# smartmeterif_2.net
KiCad netlist of a schematic drawn in EAGLE
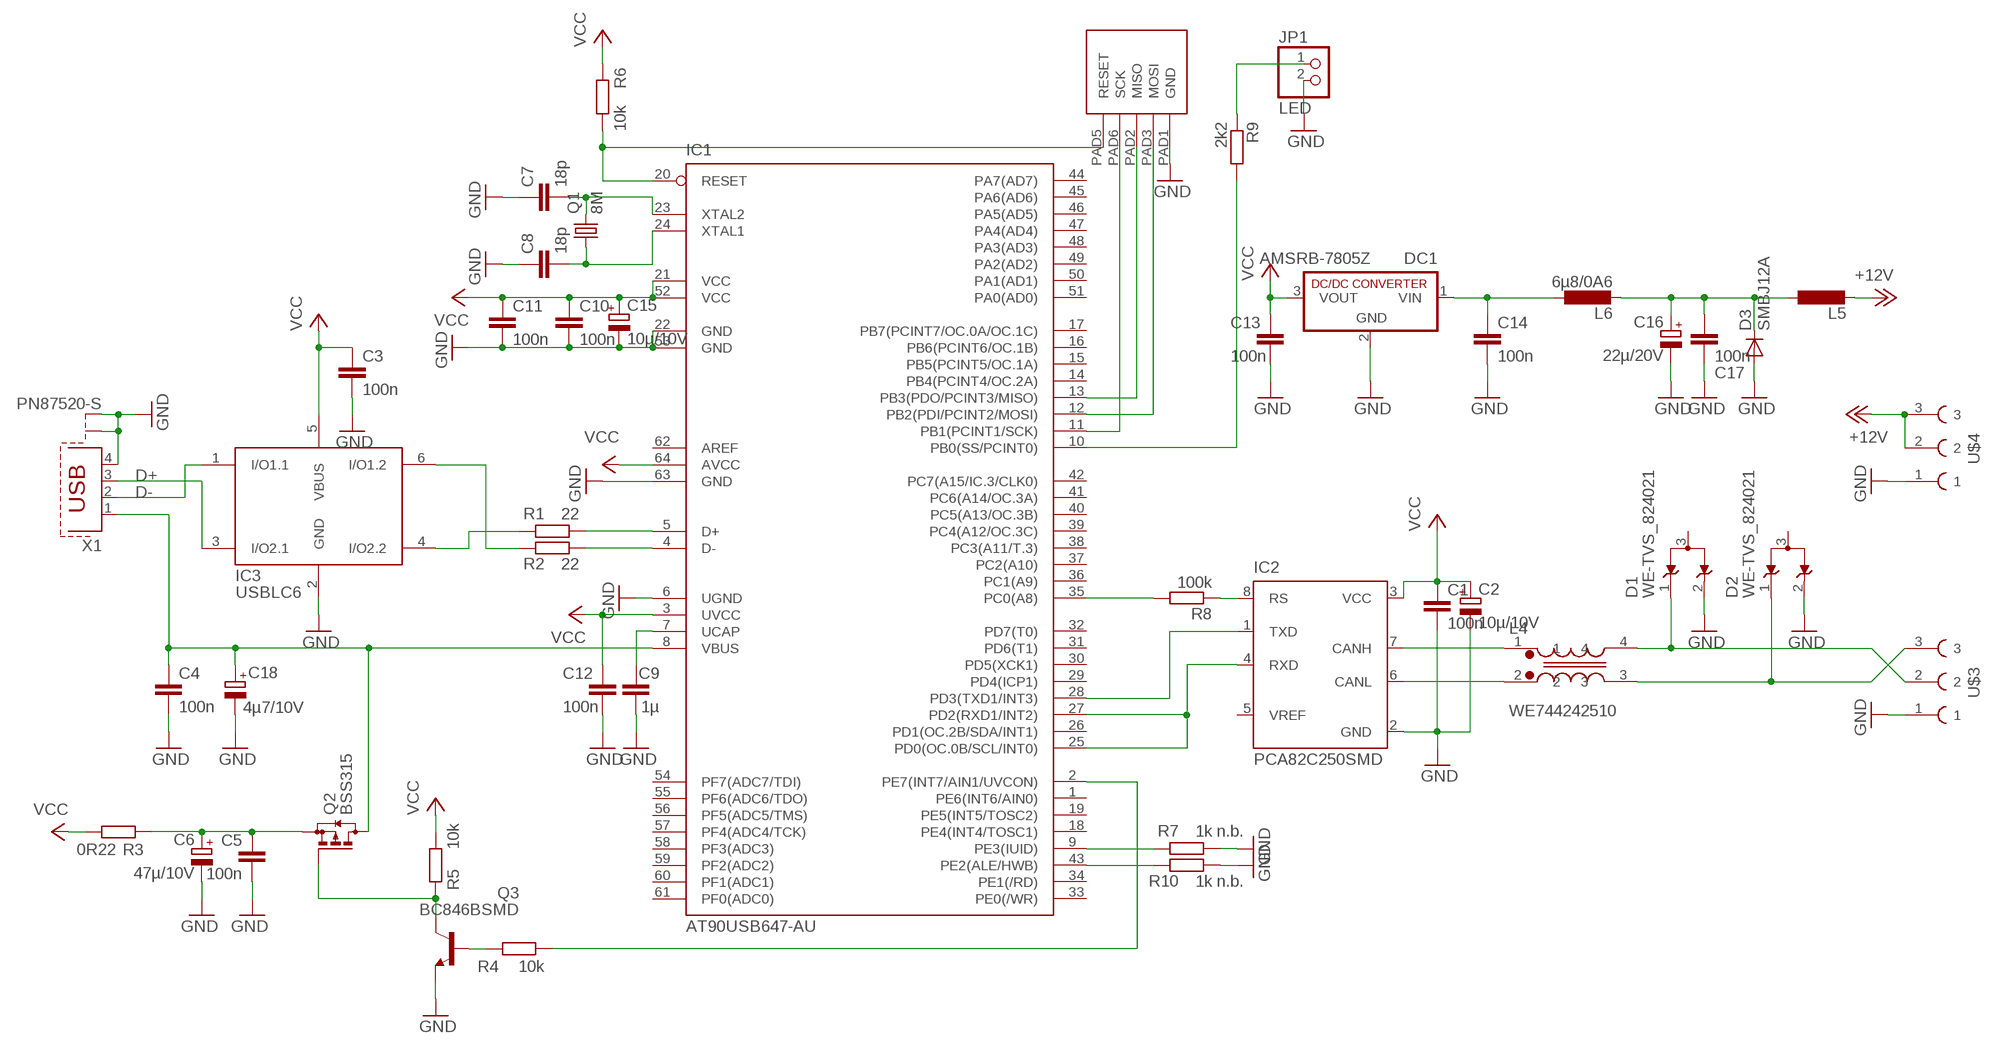
[diagram p0: schematic, sheet 1]

(export (version "E")
  (design (tool "Eeschema 10.0.6"))
  (components
    (comp (ref "C1")
      (value "100n")
      (footprint "eagle-import:C0603")
      (libsource (lib "eagle-import") (part "resistor_C-EUC0603"))
    )
    (comp (ref "C2")
      (value "10µ/10V")
      (footprint "eagle-import:A_3216-18W")
      (libsource (lib "eagle-import") (part "CPOL-EUA/3216-18W"))
    )
    (comp (ref "C3")
      (value "100n")
      (footprint "eagle-import:C0603")
      (libsource (lib "eagle-import") (part "resistor_C-EUC0603"))
    )
    (comp (ref "C4")
      (value "100n")
      (footprint "eagle-import:C0603")
      (libsource (lib "eagle-import") (part "resistor_C-EUC0603"))
    )
    (comp (ref "C5")
      (value "100n")
      (footprint "eagle-import:C0603")
      (libsource (lib "eagle-import") (part "resistor_C-EUC0603"))
    )
    (comp (ref "C6")
      (value "47µ/10V")
      (footprint "eagle-import:SMC_C")
      (libsource (lib "eagle-import") (part "CPOL-EUSMCC"))
    )
    (comp (ref "C7")
      (value "18p")
      (footprint "eagle-import:C0603")
      (libsource (lib "eagle-import") (part "C-EUC0603"))
    )
    (comp (ref "C8")
      (value "18p")
      (footprint "eagle-import:C0603")
      (libsource (lib "eagle-import") (part "C-EUC0603"))
    )
    (comp (ref "C9")
      (value "1µ")
      (footprint "eagle-import:C1210K")
      (libsource (lib "eagle-import") (part "C-EUC1210K"))
    )
    (comp (ref "C10")
      (value "100n")
      (footprint "eagle-import:C0603")
      (libsource (lib "eagle-import") (part "resistor_C-EUC0603"))
    )
    (comp (ref "C11")
      (value "100n")
      (footprint "eagle-import:C0603")
      (libsource (lib "eagle-import") (part "resistor_C-EUC0603"))
    )
    (comp (ref "C12")
      (value "100n")
      (footprint "eagle-import:C0603")
      (libsource (lib "eagle-import") (part "resistor_C-EUC0603"))
    )
    (comp (ref "C13")
      (value "100n")
      (footprint "eagle-import:C0603")
      (libsource (lib "eagle-import") (part "resistor_C-EUC0603"))
    )
    (comp (ref "C14")
      (value "100n")
      (footprint "eagle-import:C0603")
      (libsource (lib "eagle-import") (part "resistor_C-EUC0603"))
    )
    (comp (ref "C15")
      (value "10µ/10V")
      (footprint "eagle-import:A_3216-18W")
      (libsource (lib "eagle-import") (part "CPOL-EUA/3216-18W"))
    )
    (comp (ref "C16")
      (value "22µ/20V")
      (footprint "eagle-import:SMC_C")
      (libsource (lib "eagle-import") (part "CPOL-EUSMCC"))
    )
    (comp (ref "C17")
      (value "100n")
      (footprint "eagle-import:C0603")
      (libsource (lib "eagle-import") (part "resistor_C-EUC0603"))
    )
    (comp (ref "C18")
      (value "4µ7/10V")
      (footprint "eagle-import:SMC_A")
      (libsource (lib "eagle-import") (part "CPOL-EUSMCA"))
    )
    (comp (ref "D1")
      (value "WE-TVS_824021")
      (footprint "eagle-import:WE-TVS_SOT23-3L")
      (libsource (lib "eagle-import") (part "WE-TVS_824021"))
    )
    (comp (ref "D2")
      (value "WE-TVS_824021")
      (footprint "eagle-import:WE-TVS_SOT23-3L")
      (libsource (lib "eagle-import") (part "WE-TVS_824021"))
    )
    (comp (ref "D3")
      (value "SMBJ12A")
      (footprint "eagle-import:SMB")
      (libsource (lib "eagle-import") (part "DIODE-SMB"))
    )
    (comp (ref "DC1")
      (value "AMSRB-7805Z")
      (footprint "eagle-import:SIP3")
      (libsource (lib "eagle-import") (part "R-78C-1.05.0"))
    )
    (comp (ref "IC1")
      (value "AT90USB647-AU")
      (footprint "eagle-import:TQFP64")
      (libsource (lib "eagle-import") (part "AT90USB647-AU"))
    )
    (comp (ref "IC2")
      (value "PCA82C250SMD")
      (footprint "eagle-import:SO8")
      (libsource (lib "eagle-import") (part "PCA82C250SMD"))
    )
    (comp (ref "IC3")
      (value "USBLC6")
      (footprint "eagle-import:SOT23-6L")
      (libsource (lib "eagle-import") (part "USBLC6"))
    )
    (comp (ref "JP1")
      (value "LED")
      (footprint "eagle-import:1X02")
      (libsource (lib "eagle-import") (part "PINHD-1X2"))
    )
    (comp (ref "L4")
      (value "WE744242510")
      (footprint "eagle-import:WE-SLM")
      (libsource (lib "eagle-import") (part "WE-SLM"))
    )
    (comp (ref "L5")
      (value "L-EUL1806")
      (footprint "eagle-import:L1806")
      (libsource (lib "eagle-import") (part "L-EUL1806"))
    )
    (comp (ref "L6")
      (value "6µ8/0A6")
      (footprint "eagle-import:L1812")
      (libsource (lib "eagle-import") (part "rcl_L-EUL1812"))
    )
    (comp (ref "Q1")
      (value "8M")
      (footprint "eagle-import:SM49")
      (libsource (lib "eagle-import") (part "CRYSTALSM49"))
    )
    (comp (ref "Q2")
      (value "BSS315")
      (footprint "eagle-import:SOT23")
      (libsource (lib "eagle-import") (part "BSS84"))
    )
    (comp (ref "Q3")
      (value "BC846BSMD")
      (footprint "eagle-import:SOT23")
      (libsource (lib "eagle-import") (part "BC846SMDB"))
    )
    (comp (ref "R1")
      (value "22")
      (footprint "eagle-import:R0603")
      (libsource (lib "eagle-import") (part "R-EU_R0603"))
    )
    (comp (ref "R2")
      (value "22")
      (footprint "eagle-import:R0603")
      (libsource (lib "eagle-import") (part "R-EU_R0603"))
    )
    (comp (ref "R3")
      (value "0R22")
      (footprint "eagle-import:R0603")
      (libsource (lib "eagle-import") (part "R-EU_R0603"))
    )
    (comp (ref "R4")
      (value "10k")
      (footprint "eagle-import:R0603")
      (libsource (lib "eagle-import") (part "R-EU_R0603"))
    )
    (comp (ref "R5")
      (value "10k")
      (footprint "eagle-import:R0603")
      (libsource (lib "eagle-import") (part "R-EU_R0603"))
    )
    (comp (ref "R6")
      (value "10k")
      (footprint "eagle-import:R0603")
      (libsource (lib "eagle-import") (part "R-EU_R0603"))
    )
    (comp (ref "R7")
      (value "1k n.b.")
      (footprint "eagle-import:R0603")
      (libsource (lib "eagle-import") (part "R-EU_R0603"))
    )
    (comp (ref "R8")
      (value "100k")
      (footprint "eagle-import:R0603")
      (libsource (lib "eagle-import") (part "resistor_R-EU_R0603"))
    )
    (comp (ref "R9")
      (value "2k2")
      (footprint "eagle-import:R0603")
      (libsource (lib "eagle-import") (part "resistor_R-EU_R0603"))
    )
    (comp (ref "R10")
      (value "1k n.b.")
      (footprint "eagle-import:R0603")
      (libsource (lib "eagle-import") (part "R-EU_R0603"))
    )
    (comp (ref "U$2")
      (value "ATMEL_ISP")
      (footprint "eagle-import:ATMEL_ISP")
      (libsource (lib "eagle-import") (part "ATMEL_ISP"))
    )
    (comp (ref "U$3")
      (value "MKDSO_2.5/3_L")
      (footprint "eagle-import:PHOENIX_MKDSO_2.5_3_L")
      (libsource (lib "eagle-import") (part "MKDSO_2.5/3_L"))
    )
    (comp (ref "U$4")
      (value "MKDSO_2.5/3_L")
      (footprint "eagle-import:PHOENIX_MKDSO_2.5_3_L")
      (libsource (lib "eagle-import") (part "MKDSO_2.5/3_L"))
    )
    (comp (ref "X1")
      (value "PN87520-S")
      (footprint "eagle-import:PN87520-S")
      (libsource (lib "eagle-import") (part "PN87520-S"))
    )
  )
  (nets
    (net (code "1") (name "+12V") (class "Default")
      (node (ref "L5") (pin "2") (pinfunction "2_2") (pintype "passive"))
      (node (ref "U$4") (pin "2") (pinfunction "2_2") (pintype "bidirectional"))
      (node (ref "U$4") (pin "3") (pinfunction "3_3") (pintype "bidirectional"))
    )
    (net (code "2") (name "/D+") (class "Default")
      (node (ref "IC3") (pin "3") (pinfunction "I/O2.1_3") (pintype "bidirectional"))
      (node (ref "X1") (pin "3") (pinfunction "3_3") (pintype "passive"))
    )
    (net (code "3") (name "/D-") (class "Default")
      (node (ref "IC3") (pin "1") (pinfunction "I/O1.1_1") (pintype "bidirectional"))
      (node (ref "X1") (pin "2") (pinfunction "2_2") (pintype "passive"))
    )
    (net (code "4") (name "GND") (class "Default")
      (node (ref "C1") (pin "2") (pinfunction "2_2") (pintype "passive"))
      (node (ref "C10") (pin "2") (pinfunction "2_2") (pintype "passive"))
      (node (ref "C11") (pin "2") (pinfunction "2_2") (pintype "passive"))
      (node (ref "C12") (pin "2") (pinfunction "2_2") (pintype "passive"))
      (node (ref "C13") (pin "2") (pinfunction "2_2") (pintype "passive"))
      (node (ref "C14") (pin "2") (pinfunction "2_2") (pintype "passive"))
      (node (ref "C15") (pin "-") (pinfunction "-_-") (pintype "passive"))
      (node (ref "C16") (pin "-") (pinfunction "-_-") (pintype "passive"))
      (node (ref "C17") (pin "2") (pinfunction "2_2") (pintype "passive"))
      (node (ref "C18") (pin "-") (pinfunction "-_-") (pintype "passive"))
      (node (ref "C2") (pin "-") (pinfunction "-_-") (pintype "passive"))
      (node (ref "C3") (pin "2") (pinfunction "2_2") (pintype "passive"))
      (node (ref "C4") (pin "2") (pinfunction "2_2") (pintype "passive"))
      (node (ref "C5") (pin "2") (pinfunction "2_2") (pintype "passive"))
      (node (ref "C6") (pin "-") (pinfunction "-_-") (pintype "passive"))
      (node (ref "C7") (pin "1") (pinfunction "1_1") (pintype "passive"))
      (node (ref "C8") (pin "1") (pinfunction "1_1") (pintype "passive"))
      (node (ref "C9") (pin "1") (pinfunction "1_1") (pintype "passive"))
      (node (ref "D1") (pin "2") (pinfunction "2_2") (pintype "passive"))
      (node (ref "D2") (pin "2") (pinfunction "2_2") (pintype "passive"))
      (node (ref "D3") (pin "A") (pinfunction "A_A") (pintype "passive"))
      (node (ref "DC1") (pin "2") (pinfunction "GND_2") (pintype "passive"))
      (node (ref "IC1") (pin "22") (pinfunction "GND_22") (pintype "power_in"))
      (node (ref "IC1") (pin "53") (pinfunction "GND_53") (pintype "power_in"))
      (node (ref "IC1") (pin "6") (pinfunction "UGND_6") (pintype "power_in"))
      (node (ref "IC1") (pin "63") (pinfunction "GND_63") (pintype "power_in"))
      (node (ref "IC2") (pin "2") (pinfunction "GND_2") (pintype "power_in"))
      (node (ref "IC3") (pin "2") (pinfunction "GND_2") (pintype "power_in"))
      (node (ref "JP1") (pin "2") (pinfunction "2_2") (pintype "passive"))
      (node (ref "Q3") (pin "2") (pinfunction "E_2") (pintype "passive"))
      (node (ref "R10") (pin "2") (pinfunction "2_2") (pintype "passive"))
      (node (ref "R7") (pin "2") (pinfunction "2_2") (pintype "passive"))
      (node (ref "U$2") (pin "PAD1") (pinfunction "GND_PAD1") (pintype "power_in"))
      (node (ref "U$3") (pin "1") (pinfunction "1_1") (pintype "bidirectional"))
      (node (ref "U$4") (pin "1") (pinfunction "1_1") (pintype "bidirectional"))
      (node (ref "X1") (pin "4") (pinfunction "4_4") (pintype "passive"))
      (node (ref "X1") (pin "S1") (pinfunction "S1_S1") (pintype "passive"))
      (node (ref "X1") (pin "S2") (pinfunction "S2_S2") (pintype "passive"))
    )
    (net (code "5") (name "Net-(C16-Pad+)") (class "Default")
      (node (ref "C16") (pin "+") (pinfunction "+_+") (pintype "passive"))
      (node (ref "C17") (pin "1") (pinfunction "1_1") (pintype "passive"))
      (node (ref "D3") (pin "C") (pinfunction "C_C") (pintype "passive"))
      (node (ref "L5") (pin "1") (pinfunction "1_1") (pintype "passive"))
      (node (ref "L6") (pin "2") (pinfunction "2_2") (pintype "passive"))
    )
    (net (code "6") (name "Net-(D1-Pad1)") (class "Default")
      (node (ref "D1") (pin "1") (pinfunction "1_1") (pintype "passive"))
      (node (ref "L4") (pin "4") (pinfunction "4_4") (pintype "bidirectional"))
      (node (ref "U$3") (pin "2") (pinfunction "2_2") (pintype "bidirectional"))
    )
    (net (code "7") (name "Net-(D2-Pad1)") (class "Default")
      (node (ref "D2") (pin "1") (pinfunction "1_1") (pintype "passive"))
      (node (ref "L4") (pin "3") (pinfunction "3_3") (pintype "bidirectional"))
      (node (ref "U$3") (pin "3") (pinfunction "3_3") (pintype "bidirectional"))
    )
    (net (code "8") (name "Net-(DC1-VIN)") (class "Default")
      (node (ref "C14") (pin "1") (pinfunction "1_1") (pintype "passive"))
      (node (ref "DC1") (pin "1") (pinfunction "VIN_1") (pintype "passive"))
      (node (ref "L6") (pin "1") (pinfunction "1_1") (pintype "passive"))
    )
    (net (code "9") (name "Net-(IC1-D+)") (class "Default")
      (node (ref "IC1") (pin "5") (pinfunction "D+_5") (pintype "bidirectional"))
      (node (ref "R1") (pin "2") (pinfunction "2_2") (pintype "passive"))
    )
    (net (code "10") (name "Net-(IC1-D-)") (class "Default")
      (node (ref "IC1") (pin "4") (pinfunction "D-_4") (pintype "bidirectional"))
      (node (ref "R2") (pin "2") (pinfunction "2_2") (pintype "passive"))
    )
    (net (code "11") (name "Net-(IC1-PB0(SS{slash}PCINT0))") (class "Default")
      (node (ref "IC1") (pin "10") (pinfunction "PB0(SS/PCINT0)_10") (pintype "bidirectional"))
      (node (ref "R9") (pin "2") (pinfunction "2_2") (pintype "passive"))
    )
    (net (code "12") (name "Net-(IC1-PB1(PCINT1{slash}SCK))") (class "Default")
      (node (ref "IC1") (pin "11") (pinfunction "PB1(PCINT1/SCK)_11") (pintype "bidirectional"))
      (node (ref "U$2") (pin "PAD6") (pinfunction "SCK_PAD6") (pintype "bidirectional"))
    )
    (net (code "13") (name "Net-(IC1-PB2(PDI{slash}PCINT2{slash}MOSI))") (class "Default")
      (node (ref "IC1") (pin "12") (pinfunction "PB2(PDI/PCINT2/MOSI)_12") (pintype "bidirectional"))
      (node (ref "U$2") (pin "PAD3") (pinfunction "MOSI_PAD3") (pintype "bidirectional"))
    )
    (net (code "14") (name "Net-(IC1-PB3(PDO{slash}PCINT3{slash}MISO))") (class "Default")
      (node (ref "IC1") (pin "13") (pinfunction "PB3(PDO/PCINT3/MISO)_13") (pintype "bidirectional"))
      (node (ref "U$2") (pin "PAD2") (pinfunction "MISO_PAD2") (pintype "bidirectional"))
    )
    (net (code "15") (name "Net-(IC1-PC0(A8))") (class "Default")
      (node (ref "IC1") (pin "35") (pinfunction "PC0(A8)_35") (pintype "bidirectional"))
      (node (ref "R8") (pin "2") (pinfunction "2_2") (pintype "passive"))
    )
    (net (code "16") (name "Net-(IC1-PD0(OC.0B{slash}SCL{slash}INT0))") (class "Default")
      (node (ref "IC1") (pin "25") (pinfunction "PD0(OC.0B/SCL/INT0)_25") (pintype "bidirectional"))
      (node (ref "IC1") (pin "27") (pinfunction "PD2(RXD1/INT2)_27") (pintype "bidirectional"))
      (node (ref "IC2") (pin "4") (pinfunction "RXD_4") (pintype "output"))
    )
    (net (code "17") (name "Net-(IC1-PD3(TXD1{slash}INT3))") (class "Default")
      (node (ref "IC1") (pin "28") (pinfunction "PD3(TXD1/INT3)_28") (pintype "bidirectional"))
      (node (ref "IC2") (pin "1") (pinfunction "TXD_1") (pintype "input"))
    )
    (net (code "18") (name "Net-(IC1-PE2(ALE{slash}HWB))") (class "Default")
      (node (ref "IC1") (pin "43") (pinfunction "PE2(ALE/HWB)_43") (pintype "bidirectional"))
      (node (ref "R10") (pin "1") (pinfunction "1_1") (pintype "passive"))
    )
    (net (code "19") (name "Net-(IC1-PE3(IUID))") (class "Default")
      (node (ref "IC1") (pin "9") (pinfunction "PE3(IUID)_9") (pintype "bidirectional"))
      (node (ref "R7") (pin "1") (pinfunction "1_1") (pintype "passive"))
    )
    (net (code "20") (name "Net-(IC1-PE7(INT7{slash}AIN1{slash}UVCON))") (class "Default")
      (node (ref "IC1") (pin "2") (pinfunction "PE7(INT7/AIN1/UVCON)_2") (pintype "bidirectional"))
      (node (ref "R4") (pin "2") (pinfunction "2_2") (pintype "passive"))
    )
    (net (code "21") (name "Net-(IC1-RESET)") (class "Default")
      (node (ref "IC1") (pin "20") (pinfunction "RESET_20") (pintype "input"))
      (node (ref "R6") (pin "2") (pinfunction "2_2") (pintype "passive"))
      (node (ref "U$2") (pin "PAD5") (pinfunction "RESET_PAD5") (pintype "bidirectional"))
    )
    (net (code "22") (name "Net-(IC1-UCAP)") (class "Default")
      (node (ref "C9") (pin "2") (pinfunction "2_2") (pintype "passive"))
      (node (ref "IC1") (pin "7") (pinfunction "UCAP_7") (pintype "power_in"))
    )
    (net (code "23") (name "Net-(IC1-VBUS)") (class "Default")
      (node (ref "C18") (pin "+") (pinfunction "+_+") (pintype "passive"))
      (node (ref "C4") (pin "1") (pinfunction "1_1") (pintype "passive"))
      (node (ref "IC1") (pin "8") (pinfunction "VBUS_8") (pintype "power_in"))
      (node (ref "Q2") (pin "3") (pinfunction "D_3") (pintype "passive"))
      (node (ref "X1") (pin "1") (pinfunction "1_1") (pintype "passive"))
    )
    (net (code "24") (name "Net-(IC1-XTAL1)") (class "Default")
      (node (ref "C8") (pin "2") (pinfunction "2_2") (pintype "passive"))
      (node (ref "IC1") (pin "24") (pinfunction "XTAL1_24") (pintype "bidirectional"))
      (node (ref "Q1") (pin "1") (pinfunction "1_1") (pintype "passive"))
    )
    (net (code "25") (name "Net-(IC1-XTAL2)") (class "Default")
      (node (ref "C7") (pin "2") (pinfunction "2_2") (pintype "passive"))
      (node (ref "IC1") (pin "23") (pinfunction "XTAL2_23") (pintype "bidirectional"))
      (node (ref "Q1") (pin "2") (pinfunction "2_2") (pintype "passive"))
    )
    (net (code "26") (name "Net-(IC2-CANH)") (class "Default")
      (node (ref "IC2") (pin "7") (pinfunction "CANH_7") (pintype "bidirectional"))
      (node (ref "L4") (pin "1") (pinfunction "1_1") (pintype "bidirectional"))
    )
    (net (code "27") (name "Net-(IC2-CANL)") (class "Default")
      (node (ref "IC2") (pin "6") (pinfunction "CANL_6") (pintype "bidirectional"))
      (node (ref "L4") (pin "2") (pinfunction "2_2") (pintype "bidirectional"))
    )
    (net (code "28") (name "Net-(IC2-RS)") (class "Default")
      (node (ref "IC2") (pin "8") (pinfunction "RS_8") (pintype "input"))
      (node (ref "R8") (pin "1") (pinfunction "1_1") (pintype "passive"))
    )
    (net (code "29") (name "Net-(IC3-I{slash}O1.2)") (class "Default")
      (node (ref "IC3") (pin "6") (pinfunction "I/O1.2_6") (pintype "bidirectional"))
      (node (ref "R2") (pin "1") (pinfunction "1_1") (pintype "passive"))
    )
    (net (code "30") (name "Net-(IC3-I{slash}O2.2)") (class "Default")
      (node (ref "IC3") (pin "4") (pinfunction "I/O2.2_4") (pintype "bidirectional"))
      (node (ref "R1") (pin "1") (pinfunction "1_1") (pintype "passive"))
    )
    (net (code "31") (name "Net-(JP1-Pad1)") (class "Default")
      (node (ref "JP1") (pin "1") (pinfunction "1_1") (pintype "passive"))
      (node (ref "R9") (pin "1") (pinfunction "1_1") (pintype "passive"))
    )
    (net (code "32") (name "Net-(Q2-G)") (class "Default")
      (node (ref "Q2") (pin "1") (pinfunction "G_1") (pintype "passive"))
      (node (ref "Q3") (pin "3") (pinfunction "C_3") (pintype "passive"))
      (node (ref "R5") (pin "1") (pinfunction "1_1") (pintype "passive"))
    )
    (net (code "33") (name "Net-(Q2-S)") (class "Default")
      (node (ref "C5") (pin "1") (pinfunction "1_1") (pintype "passive"))
      (node (ref "C6") (pin "+") (pinfunction "+_+") (pintype "passive"))
      (node (ref "Q2") (pin "2") (pinfunction "S_2") (pintype "passive"))
      (node (ref "R3") (pin "1") (pinfunction "1_1") (pintype "passive"))
    )
    (net (code "34") (name "Net-(Q3-B)") (class "Default")
      (node (ref "Q3") (pin "1") (pinfunction "B_1") (pintype "passive"))
      (node (ref "R4") (pin "1") (pinfunction "1_1") (pintype "passive"))
    )
    (net (code "35") (name "VCC") (class "Default")
      (node (ref "C1") (pin "1") (pinfunction "1_1") (pintype "passive"))
      (node (ref "C10") (pin "1") (pinfunction "1_1") (pintype "passive"))
      (node (ref "C11") (pin "1") (pinfunction "1_1") (pintype "passive"))
      (node (ref "C12") (pin "1") (pinfunction "1_1") (pintype "passive"))
      (node (ref "C13") (pin "1") (pinfunction "1_1") (pintype "passive"))
      (node (ref "C15") (pin "+") (pinfunction "+_+") (pintype "passive"))
      (node (ref "C2") (pin "+") (pinfunction "+_+") (pintype "passive"))
      (node (ref "C3") (pin "1") (pinfunction "1_1") (pintype "passive"))
      (node (ref "DC1") (pin "3") (pinfunction "VOUT_3") (pintype "passive"))
      (node (ref "IC1") (pin "21") (pinfunction "VCC_21") (pintype "power_in"))
      (node (ref "IC1") (pin "3") (pinfunction "UVCC_3") (pintype "power_in"))
      (node (ref "IC1") (pin "52") (pinfunction "VCC_52") (pintype "power_in"))
      (node (ref "IC1") (pin "64") (pinfunction "AVCC_64") (pintype "bidirectional"))
      (node (ref "IC2") (pin "3") (pinfunction "VCC_3") (pintype "power_in"))
      (node (ref "IC3") (pin "5") (pinfunction "VBUS_5") (pintype "power_in"))
      (node (ref "R3") (pin "2") (pinfunction "2_2") (pintype "passive"))
      (node (ref "R5") (pin "2") (pinfunction "2_2") (pintype "passive"))
      (node (ref "R6") (pin "1") (pinfunction "1_1") (pintype "passive"))
    )
    (net (code "36") (name "unconnected-(D1-GND-Pad3)") (class "Default")
      (node (ref "D1") (pin "3") (pinfunction "GND_3") (pintype "passive"))
    )
    (net (code "37") (name "unconnected-(D2-GND-Pad3)") (class "Default")
      (node (ref "D2") (pin "3") (pinfunction "GND_3") (pintype "passive"))
    )
    (net (code "38") (name "unconnected-(IC1-AREF-Pad62)") (class "Default")
      (node (ref "IC1") (pin "62") (pinfunction "AREF_62") (pintype "bidirectional"))
    )
    (net (code "39") (name "unconnected-(IC1-PA0(AD0)-Pad51)") (class "Default")
      (node (ref "IC1") (pin "51") (pinfunction "PA0(AD0)_51") (pintype "bidirectional"))
    )
    (net (code "40") (name "unconnected-(IC1-PA1(AD1)-Pad50)") (class "Default")
      (node (ref "IC1") (pin "50") (pinfunction "PA1(AD1)_50") (pintype "bidirectional"))
    )
    (net (code "41") (name "unconnected-(IC1-PA2(AD2)-Pad49)") (class "Default")
      (node (ref "IC1") (pin "49") (pinfunction "PA2(AD2)_49") (pintype "bidirectional"))
    )
    (net (code "42") (name "unconnected-(IC1-PA3(AD3)-Pad48)") (class "Default")
      (node (ref "IC1") (pin "48") (pinfunction "PA3(AD3)_48") (pintype "bidirectional"))
    )
    (net (code "43") (name "unconnected-(IC1-PA4(AD4)-Pad47)") (class "Default")
      (node (ref "IC1") (pin "47") (pinfunction "PA4(AD4)_47") (pintype "bidirectional"))
    )
    (net (code "44") (name "unconnected-(IC1-PA5(AD5)-Pad46)") (class "Default")
      (node (ref "IC1") (pin "46") (pinfunction "PA5(AD5)_46") (pintype "bidirectional"))
    )
    (net (code "45") (name "unconnected-(IC1-PA6(AD6)-Pad45)") (class "Default")
      (node (ref "IC1") (pin "45") (pinfunction "PA6(AD6)_45") (pintype "bidirectional"))
    )
    (net (code "46") (name "unconnected-(IC1-PA7(AD7)-Pad44)") (class "Default")
      (node (ref "IC1") (pin "44") (pinfunction "PA7(AD7)_44") (pintype "bidirectional"))
    )
    (net (code "47") (name "unconnected-(IC1-PB4(PCINT4{slash}OC.2A)-Pad14)") (class "Default")
      (node (ref "IC1") (pin "14") (pinfunction "PB4(PCINT4/OC.2A)_14") (pintype "bidirectional"))
    )
    (net (code "48") (name "unconnected-(IC1-PB5(PCINT5{slash}OC.1A)-Pad15)") (class "Default")
      (node (ref "IC1") (pin "15") (pinfunction "PB5(PCINT5/OC.1A)_15") (pintype "bidirectional"))
    )
    (net (code "49") (name "unconnected-(IC1-PB6(PCINT6{slash}OC.1B)-Pad16)") (class "Default")
      (node (ref "IC1") (pin "16") (pinfunction "PB6(PCINT6/OC.1B)_16") (pintype "bidirectional"))
    )
    (net (code "50") (name "unconnected-(IC1-PB7(PCINT7{slash}OC.0A{slash}OC.1C)-Pad17)") (class "Default")
      (node (ref "IC1") (pin "17") (pinfunction "PB7(PCINT7/OC.0A/OC.1C)_17") (pintype "bidirectional"))
    )
    (net (code "51") (name "unconnected-(IC1-PC1(A9)-Pad36)") (class "Default")
      (node (ref "IC1") (pin "36") (pinfunction "PC1(A9)_36") (pintype "bidirectional"))
    )
    (net (code "52") (name "unconnected-(IC1-PC2(A10)-Pad37)") (class "Default")
      (node (ref "IC1") (pin "37") (pinfunction "PC2(A10)_37") (pintype "bidirectional"))
    )
    (net (code "53") (name "unconnected-(IC1-PC3(A11{slash}T.3)-Pad38)") (class "Default")
      (node (ref "IC1") (pin "38") (pinfunction "PC3(A11/T.3)_38") (pintype "bidirectional"))
    )
    (net (code "54") (name "unconnected-(IC1-PC4(A12{slash}OC.3C)-Pad39)") (class "Default")
      (node (ref "IC1") (pin "39") (pinfunction "PC4(A12/OC.3C)_39") (pintype "bidirectional"))
    )
    (net (code "55") (name "unconnected-(IC1-PC5(A13{slash}OC.3B)-Pad40)") (class "Default")
      (node (ref "IC1") (pin "40") (pinfunction "PC5(A13/OC.3B)_40") (pintype "bidirectional"))
    )
    (net (code "56") (name "unconnected-(IC1-PC6(A14{slash}OC.3A)-Pad41)") (class "Default")
      (node (ref "IC1") (pin "41") (pinfunction "PC6(A14/OC.3A)_41") (pintype "bidirectional"))
    )
    (net (code "57") (name "unconnected-(IC1-PC7(A15{slash}IC.3{slash}CLK0)-Pad42)") (class "Default")
      (node (ref "IC1") (pin "42") (pinfunction "PC7(A15/IC.3/CLK0)_42") (pintype "bidirectional"))
    )
    (net (code "58") (name "unconnected-(IC1-PD1(OC.2B{slash}SDA{slash}INT1)-Pad26)") (class "Default")
      (node (ref "IC1") (pin "26") (pinfunction "PD1(OC.2B/SDA/INT1)_26") (pintype "bidirectional"))
    )
    (net (code "59") (name "unconnected-(IC1-PD4(ICP1)-Pad29)") (class "Default")
      (node (ref "IC1") (pin "29") (pinfunction "PD4(ICP1)_29") (pintype "bidirectional"))
    )
    (net (code "60") (name "unconnected-(IC1-PD5(XCK1)-Pad30)") (class "Default")
      (node (ref "IC1") (pin "30") (pinfunction "PD5(XCK1)_30") (pintype "bidirectional"))
    )
    (net (code "61") (name "unconnected-(IC1-PD6(T1)-Pad31)") (class "Default")
      (node (ref "IC1") (pin "31") (pinfunction "PD6(T1)_31") (pintype "bidirectional"))
    )
    (net (code "62") (name "unconnected-(IC1-PD7(T0)-Pad32)") (class "Default")
      (node (ref "IC1") (pin "32") (pinfunction "PD7(T0)_32") (pintype "bidirectional"))
    )
    (net (code "63") (name "unconnected-(IC1-PE0({slash}WR)-Pad33)") (class "Default")
      (node (ref "IC1") (pin "33") (pinfunction "PE0(/WR)_33") (pintype "bidirectional"))
    )
    (net (code "64") (name "unconnected-(IC1-PE1({slash}RD)-Pad34)") (class "Default")
      (node (ref "IC1") (pin "34") (pinfunction "PE1(/RD)_34") (pintype "bidirectional"))
    )
    (net (code "65") (name "unconnected-(IC1-PE4(INT4{slash}TOSC1)-Pad18)") (class "Default")
      (node (ref "IC1") (pin "18") (pinfunction "PE4(INT4/TOSC1)_18") (pintype "bidirectional"))
    )
    (net (code "66") (name "unconnected-(IC1-PE5(INT5{slash}TOSC2)-Pad19)") (class "Default")
      (node (ref "IC1") (pin "19") (pinfunction "PE5(INT5/TOSC2)_19") (pintype "bidirectional"))
    )
    (net (code "67") (name "unconnected-(IC1-PE6(INT6{slash}AIN0)-Pad1)") (class "Default")
      (node (ref "IC1") (pin "1") (pinfunction "PE6(INT6/AIN0)_1") (pintype "bidirectional"))
    )
    (net (code "68") (name "unconnected-(IC1-PF0(ADC0)-Pad61)") (class "Default")
      (node (ref "IC1") (pin "61") (pinfunction "PF0(ADC0)_61") (pintype "bidirectional"))
    )
    (net (code "69") (name "unconnected-(IC1-PF1(ADC1)-Pad60)") (class "Default")
      (node (ref "IC1") (pin "60") (pinfunction "PF1(ADC1)_60") (pintype "bidirectional"))
    )
    (net (code "70") (name "unconnected-(IC1-PF2(ADC2)-Pad59)") (class "Default")
      (node (ref "IC1") (pin "59") (pinfunction "PF2(ADC2)_59") (pintype "bidirectional"))
    )
    (net (code "71") (name "unconnected-(IC1-PF3(ADC3)-Pad58)") (class "Default")
      (node (ref "IC1") (pin "58") (pinfunction "PF3(ADC3)_58") (pintype "bidirectional"))
    )
    (net (code "72") (name "unconnected-(IC1-PF4(ADC4{slash}TCK)-Pad57)") (class "Default")
      (node (ref "IC1") (pin "57") (pinfunction "PF4(ADC4/TCK)_57") (pintype "bidirectional"))
    )
    (net (code "73") (name "unconnected-(IC1-PF5(ADC5{slash}TMS)-Pad56)") (class "Default")
      (node (ref "IC1") (pin "56") (pinfunction "PF5(ADC5/TMS)_56") (pintype "bidirectional"))
    )
    (net (code "74") (name "unconnected-(IC1-PF6(ADC6{slash}TDO)-Pad55)") (class "Default")
      (node (ref "IC1") (pin "55") (pinfunction "PF6(ADC6/TDO)_55") (pintype "bidirectional"))
    )
    (net (code "75") (name "unconnected-(IC1-PF7(ADC7{slash}TDI)-Pad54)") (class "Default")
      (node (ref "IC1") (pin "54") (pinfunction "PF7(ADC7/TDI)_54") (pintype "bidirectional"))
    )
    (net (code "76") (name "unconnected-(IC2-VREF-Pad5)") (class "Default")
      (node (ref "IC2") (pin "5") (pinfunction "VREF_5") (pintype "output"))
    )
  )
)
